# untitled.net
KiCad netlist of a schematic drawn in EAGLE
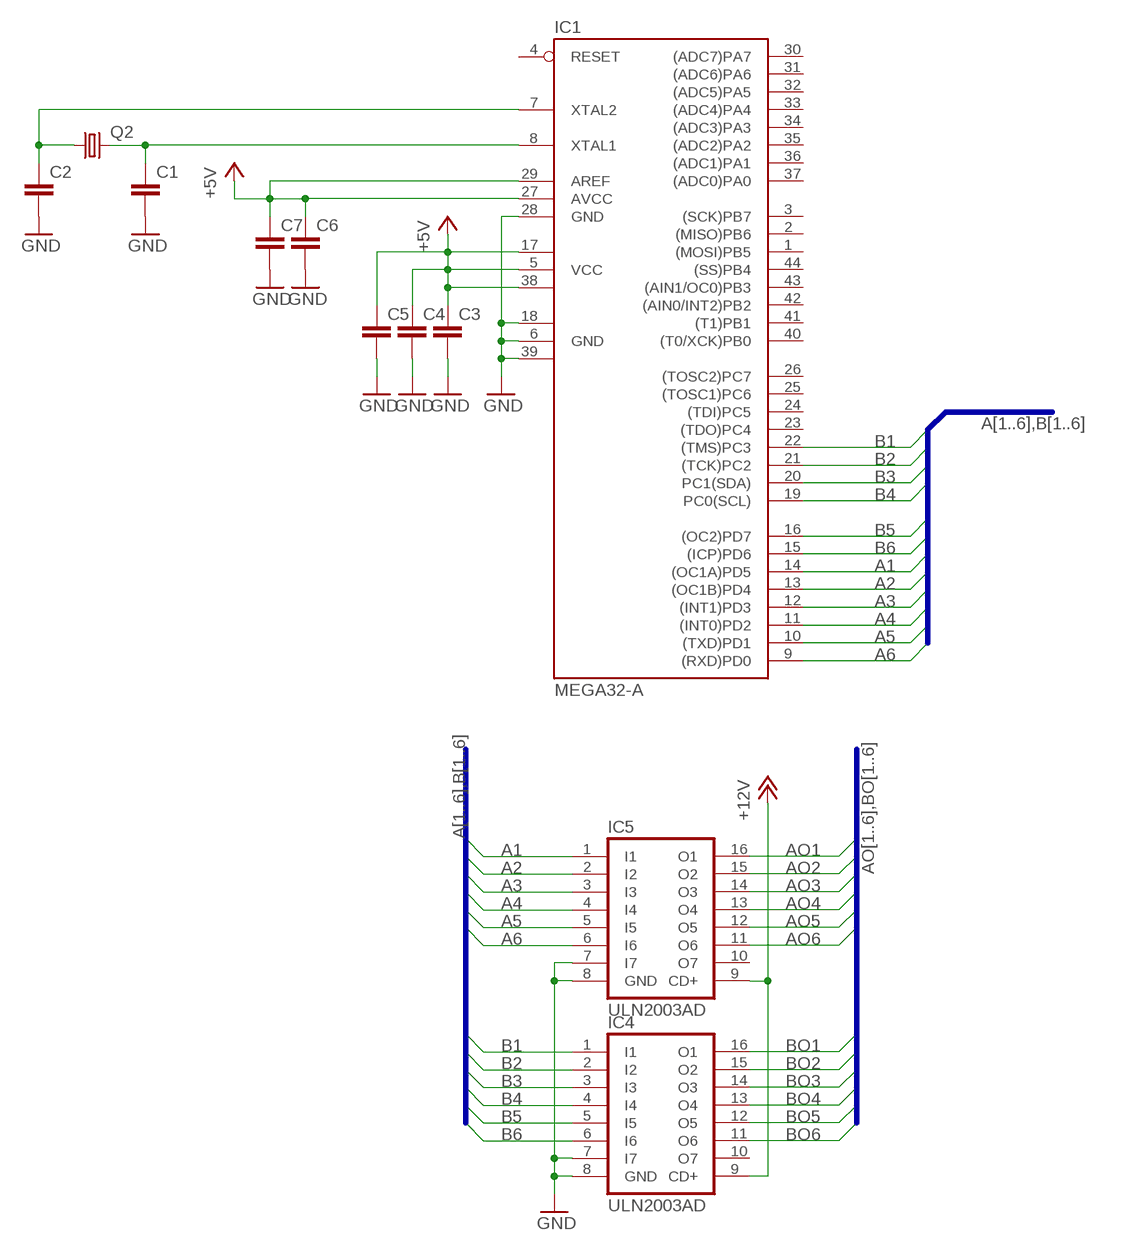
[diagram p0: schematic, sheet 1]

(export (version "E")
  (design (tool "Eeschema 10.0.6"))
  (components
    (comp (ref "C1")
      (value "C-EUC0805K")
      (footprint "eagle-import:C0805K")
      (libsource (lib "eagle-import") (part "C-EUC0805K"))
    )
    (comp (ref "C2")
      (value "C-EUC0805K")
      (footprint "eagle-import:C0805K")
      (libsource (lib "eagle-import") (part "C-EUC0805K"))
    )
    (comp (ref "C3")
      (value "C-EUC0805K")
      (footprint "eagle-import:C0805K")
      (libsource (lib "eagle-import") (part "C-EUC0805K"))
    )
    (comp (ref "C4")
      (value "C-EUC0805K")
      (footprint "eagle-import:C0805K")
      (libsource (lib "eagle-import") (part "C-EUC0805K"))
    )
    (comp (ref "C5")
      (value "C-EUC0805K")
      (footprint "eagle-import:C0805K")
      (libsource (lib "eagle-import") (part "C-EUC0805K"))
    )
    (comp (ref "C6")
      (value "C-EUC0805K")
      (footprint "eagle-import:C0805K")
      (libsource (lib "eagle-import") (part "C-EUC0805K"))
    )
    (comp (ref "C7")
      (value "C-EUC0805K")
      (footprint "eagle-import:C0805K")
      (libsource (lib "eagle-import") (part "C-EUC0805K"))
    )
    (comp (ref "IC1")
      (value "MEGA32-A")
      (footprint "eagle-import:TQFP44")
      (fields (field (name "MPN") "ATMEGA32-16AU"))
      (libsource (lib "eagle-import") (part "MEGA32-A"))
    )
    (comp (ref "IC4")
      (value "ULN2003AD")
      (footprint "eagle-import:SO16")
      (libsource (lib "eagle-import") (part "ULN2003AD"))
    )
    (comp (ref "IC5")
      (value "ULN2003AD")
      (footprint "eagle-import:SO16")
      (libsource (lib "eagle-import") (part "ULN2003AD"))
    )
    (comp (ref "Q2")
      (value "CRYSTALSM49")
      (footprint "eagle-import:SM49")
      (libsource (lib "eagle-import") (part "CRYSTALSM49"))
    )
  )
  (nets
    (net (code "1") (name "+5V") (class "Default")
      (node (ref "C3") (pin "1") (pinfunction "1_1") (pintype "passive"))
      (node (ref "C4") (pin "1") (pinfunction "1_1") (pintype "passive"))
      (node (ref "C5") (pin "1") (pinfunction "1_1") (pintype "passive"))
      (node (ref "C6") (pin "1") (pinfunction "1_1") (pintype "passive"))
      (node (ref "C7") (pin "1") (pinfunction "1_1") (pintype "passive"))
      (node (ref "IC1") (pin "17") (pinfunction "VCC1_17") (pintype "power_in"))
      (node (ref "IC1") (pin "27") (pinfunction "AVCC_27") (pintype "power_in"))
      (node (ref "IC1") (pin "29") (pinfunction "AREF_29") (pintype "passive"))
      (node (ref "IC1") (pin "38") (pinfunction "VCC2_38") (pintype "power_in"))
      (node (ref "IC1") (pin "5") (pinfunction "VCC_5") (pintype "power_in"))
    )
    (net (code "2") (name "+12V") (class "Default")
      (node (ref "IC4") (pin "9") (pinfunction "CD+_9") (pintype "passive"))
      (node (ref "IC5") (pin "9") (pinfunction "CD+_9") (pintype "passive"))
    )
    (net (code "3") (name "/A1") (class "Default")
      (node (ref "IC1") (pin "14") (pinfunction "(OC1A)PD5_14") (pintype "bidirectional"))
      (node (ref "IC5") (pin "1") (pinfunction "I1_1") (pintype "input"))
    )
    (net (code "4") (name "/A2") (class "Default")
      (node (ref "IC1") (pin "13") (pinfunction "(OC1B)PD4_13") (pintype "bidirectional"))
      (node (ref "IC5") (pin "2") (pinfunction "I2_2") (pintype "input"))
    )
    (net (code "5") (name "/A3") (class "Default")
      (node (ref "IC1") (pin "12") (pinfunction "(INT1)PD3_12") (pintype "bidirectional"))
      (node (ref "IC5") (pin "3") (pinfunction "I3_3") (pintype "input"))
    )
    (net (code "6") (name "/A4") (class "Default")
      (node (ref "IC1") (pin "11") (pinfunction "(INT0)PD2_11") (pintype "bidirectional"))
      (node (ref "IC5") (pin "4") (pinfunction "I4_4") (pintype "input"))
    )
    (net (code "7") (name "/A5") (class "Default")
      (node (ref "IC1") (pin "10") (pinfunction "(TXD)PD1_10") (pintype "bidirectional"))
      (node (ref "IC5") (pin "5") (pinfunction "I5_5") (pintype "input"))
    )
    (net (code "8") (name "/A6") (class "Default")
      (node (ref "IC1") (pin "9") (pinfunction "(RXD)PD0_9") (pintype "bidirectional"))
      (node (ref "IC5") (pin "6") (pinfunction "I6_6") (pintype "input"))
    )
    (net (code "9") (name "/AO1") (class "Default")
      (node (ref "IC5") (pin "16") (pinfunction "O1_16") (pintype "open_collector"))
    )
    (net (code "10") (name "/AO2") (class "Default")
      (node (ref "IC5") (pin "15") (pinfunction "O2_15") (pintype "open_collector"))
    )
    (net (code "11") (name "/AO3") (class "Default")
      (node (ref "IC5") (pin "14") (pinfunction "O3_14") (pintype "open_collector"))
    )
    (net (code "12") (name "/AO4") (class "Default")
      (node (ref "IC5") (pin "13") (pinfunction "O4_13") (pintype "open_collector"))
    )
    (net (code "13") (name "/AO5") (class "Default")
      (node (ref "IC5") (pin "12") (pinfunction "O5_12") (pintype "open_collector"))
    )
    (net (code "14") (name "/AO6") (class "Default")
      (node (ref "IC5") (pin "11") (pinfunction "O6_11") (pintype "open_collector"))
    )
    (net (code "15") (name "/B1") (class "Default")
      (node (ref "IC1") (pin "22") (pinfunction "(TMS)PC3_22") (pintype "bidirectional"))
      (node (ref "IC4") (pin "1") (pinfunction "I1_1") (pintype "input"))
    )
    (net (code "16") (name "/B2") (class "Default")
      (node (ref "IC1") (pin "21") (pinfunction "(TCK)PC2_21") (pintype "bidirectional"))
      (node (ref "IC4") (pin "2") (pinfunction "I2_2") (pintype "input"))
    )
    (net (code "17") (name "/B3") (class "Default")
      (node (ref "IC1") (pin "20") (pinfunction "PC1(SDA)_20") (pintype "bidirectional"))
      (node (ref "IC4") (pin "3") (pinfunction "I3_3") (pintype "input"))
    )
    (net (code "18") (name "/B4") (class "Default")
      (node (ref "IC1") (pin "19") (pinfunction "PC0(SCL)_19") (pintype "bidirectional"))
      (node (ref "IC4") (pin "4") (pinfunction "I4_4") (pintype "input"))
    )
    (net (code "19") (name "/B5") (class "Default")
      (node (ref "IC1") (pin "16") (pinfunction "(OC2)PD7_16") (pintype "bidirectional"))
      (node (ref "IC4") (pin "5") (pinfunction "I5_5") (pintype "input"))
    )
    (net (code "20") (name "/B6") (class "Default")
      (node (ref "IC1") (pin "15") (pinfunction "(ICP)PD6_15") (pintype "bidirectional"))
      (node (ref "IC4") (pin "6") (pinfunction "I6_6") (pintype "input"))
    )
    (net (code "21") (name "/BO1") (class "Default")
      (node (ref "IC4") (pin "16") (pinfunction "O1_16") (pintype "open_collector"))
    )
    (net (code "22") (name "/BO2") (class "Default")
      (node (ref "IC4") (pin "15") (pinfunction "O2_15") (pintype "open_collector"))
    )
    (net (code "23") (name "/BO3") (class "Default")
      (node (ref "IC4") (pin "14") (pinfunction "O3_14") (pintype "open_collector"))
    )
    (net (code "24") (name "/BO4") (class "Default")
      (node (ref "IC4") (pin "13") (pinfunction "O4_13") (pintype "open_collector"))
    )
    (net (code "25") (name "/BO5") (class "Default")
      (node (ref "IC4") (pin "12") (pinfunction "O5_12") (pintype "open_collector"))
    )
    (net (code "26") (name "/BO6") (class "Default")
      (node (ref "IC4") (pin "11") (pinfunction "O6_11") (pintype "open_collector"))
    )
    (net (code "29") (name "GND") (class "Default")
      (node (ref "C1") (pin "2") (pinfunction "2_2") (pintype "passive"))
      (node (ref "C2") (pin "2") (pinfunction "2_2") (pintype "passive"))
      (node (ref "C3") (pin "2") (pinfunction "2_2") (pintype "passive"))
      (node (ref "C4") (pin "2") (pinfunction "2_2") (pintype "passive"))
      (node (ref "C5") (pin "2") (pinfunction "2_2") (pintype "passive"))
      (node (ref "C6") (pin "2") (pinfunction "2_2") (pintype "passive"))
      (node (ref "C7") (pin "2") (pinfunction "2_2") (pintype "passive"))
      (node (ref "IC1") (pin "18") (pinfunction "GND1_18") (pintype "power_in"))
      (node (ref "IC1") (pin "28") (pinfunction "GND_28") (pintype "power_in"))
      (node (ref "IC1") (pin "39") (pinfunction "GND2_39") (pintype "power_in"))
      (node (ref "IC1") (pin "6") (pinfunction "GND_6") (pintype "power_in"))
      (node (ref "IC4") (pin "7") (pinfunction "I7_7") (pintype "input"))
      (node (ref "IC4") (pin "8") (pinfunction "GND_8") (pintype "power_in"))
      (node (ref "IC5") (pin "7") (pinfunction "I7_7") (pintype "input"))
      (node (ref "IC5") (pin "8") (pinfunction "GND_8") (pintype "power_in"))
    )
    (net (code "30") (name "Net-(IC1-XTAL1)") (class "Default")
      (node (ref "C1") (pin "1") (pinfunction "1_1") (pintype "passive"))
      (node (ref "IC1") (pin "8") (pinfunction "XTAL1_8") (pintype "bidirectional"))
      (node (ref "Q2") (pin "2") (pinfunction "2_2") (pintype "passive"))
    )
    (net (code "31") (name "Net-(IC1-XTAL2)") (class "Default")
      (node (ref "C2") (pin "1") (pinfunction "1_1") (pintype "passive"))
      (node (ref "IC1") (pin "7") (pinfunction "XTAL2_7") (pintype "bidirectional"))
      (node (ref "Q2") (pin "1") (pinfunction "1_1") (pintype "passive"))
    )
    (net (code "32") (name "unconnected-(IC1-(ADC0)PA0-Pad37)") (class "Default")
      (node (ref "IC1") (pin "37") (pinfunction "(ADC0)PA0_37") (pintype "bidirectional"))
    )
    (net (code "33") (name "unconnected-(IC1-(ADC1)PA1-Pad36)") (class "Default")
      (node (ref "IC1") (pin "36") (pinfunction "(ADC1)PA1_36") (pintype "bidirectional"))
    )
    (net (code "34") (name "unconnected-(IC1-(ADC2)PA2-Pad35)") (class "Default")
      (node (ref "IC1") (pin "35") (pinfunction "(ADC2)PA2_35") (pintype "bidirectional"))
    )
    (net (code "35") (name "unconnected-(IC1-(ADC3)PA3-Pad34)") (class "Default")
      (node (ref "IC1") (pin "34") (pinfunction "(ADC3)PA3_34") (pintype "bidirectional"))
    )
    (net (code "36") (name "unconnected-(IC1-(ADC4)PA4-Pad33)") (class "Default")
      (node (ref "IC1") (pin "33") (pinfunction "(ADC4)PA4_33") (pintype "bidirectional"))
    )
    (net (code "37") (name "unconnected-(IC1-(ADC5)PA5-Pad32)") (class "Default")
      (node (ref "IC1") (pin "32") (pinfunction "(ADC5)PA5_32") (pintype "bidirectional"))
    )
    (net (code "38") (name "unconnected-(IC1-(ADC6)PA6-Pad31)") (class "Default")
      (node (ref "IC1") (pin "31") (pinfunction "(ADC6)PA6_31") (pintype "bidirectional"))
    )
    (net (code "39") (name "unconnected-(IC1-(ADC7)PA7-Pad30)") (class "Default")
      (node (ref "IC1") (pin "30") (pinfunction "(ADC7)PA7_30") (pintype "bidirectional"))
    )
    (net (code "40") (name "unconnected-(IC1-(AIN0{slash}INT2)PB2-Pad42)") (class "Default")
      (node (ref "IC1") (pin "42") (pinfunction "(AIN0/INT2)PB2_42") (pintype "bidirectional"))
    )
    (net (code "41") (name "unconnected-(IC1-(AIN1{slash}OC0)PB3-Pad43)") (class "Default")
      (node (ref "IC1") (pin "43") (pinfunction "(AIN1/OC0)PB3_43") (pintype "bidirectional"))
    )
    (net (code "42") (name "unconnected-(IC1-(MISO)PB6-Pad2)") (class "Default")
      (node (ref "IC1") (pin "2") (pinfunction "(MISO)PB6_2") (pintype "bidirectional"))
    )
    (net (code "43") (name "unconnected-(IC1-(MOSI)PB5-Pad1)") (class "Default")
      (node (ref "IC1") (pin "1") (pinfunction "(MOSI)PB5_1") (pintype "bidirectional"))
    )
    (net (code "44") (name "unconnected-(IC1-(SCK)PB7-Pad3)") (class "Default")
      (node (ref "IC1") (pin "3") (pinfunction "(SCK)PB7_3") (pintype "bidirectional"))
    )
    (net (code "45") (name "unconnected-(IC1-(SS)PB4-Pad44)") (class "Default")
      (node (ref "IC1") (pin "44") (pinfunction "(SS)PB4_44") (pintype "bidirectional"))
    )
    (net (code "46") (name "unconnected-(IC1-(T0{slash}XCK)PB0-Pad40)") (class "Default")
      (node (ref "IC1") (pin "40") (pinfunction "(T0/XCK)PB0_40") (pintype "bidirectional"))
    )
    (net (code "47") (name "unconnected-(IC1-(T1)PB1-Pad41)") (class "Default")
      (node (ref "IC1") (pin "41") (pinfunction "(T1)PB1_41") (pintype "bidirectional"))
    )
    (net (code "48") (name "unconnected-(IC1-(TDI)PC5-Pad24)") (class "Default")
      (node (ref "IC1") (pin "24") (pinfunction "(TDI)PC5_24") (pintype "bidirectional"))
    )
    (net (code "49") (name "unconnected-(IC1-(TDO)PC4-Pad23)") (class "Default")
      (node (ref "IC1") (pin "23") (pinfunction "(TDO)PC4_23") (pintype "bidirectional"))
    )
    (net (code "50") (name "unconnected-(IC1-(TOSC1)PC6-Pad25)") (class "Default")
      (node (ref "IC1") (pin "25") (pinfunction "(TOSC1)PC6_25") (pintype "bidirectional"))
    )
    (net (code "51") (name "unconnected-(IC1-(TOSC2)PC7-Pad26)") (class "Default")
      (node (ref "IC1") (pin "26") (pinfunction "(TOSC2)PC7_26") (pintype "bidirectional"))
    )
    (net (code "52") (name "unconnected-(IC1-RESET-Pad4)") (class "Default")
      (node (ref "IC1") (pin "4") (pinfunction "RESET_4") (pintype "input"))
    )
    (net (code "53") (name "unconnected-(IC4-O7-Pad10)") (class "Default")
      (node (ref "IC4") (pin "10") (pinfunction "O7_10") (pintype "open_collector"))
    )
    (net (code "54") (name "unconnected-(IC5-O7-Pad10)") (class "Default")
      (node (ref "IC5") (pin "10") (pinfunction "O7_10") (pintype "open_collector"))
    )
  )
)
